# Controller_Sheet.net
KiCad netlist of a schematic drawn in Altium Designer
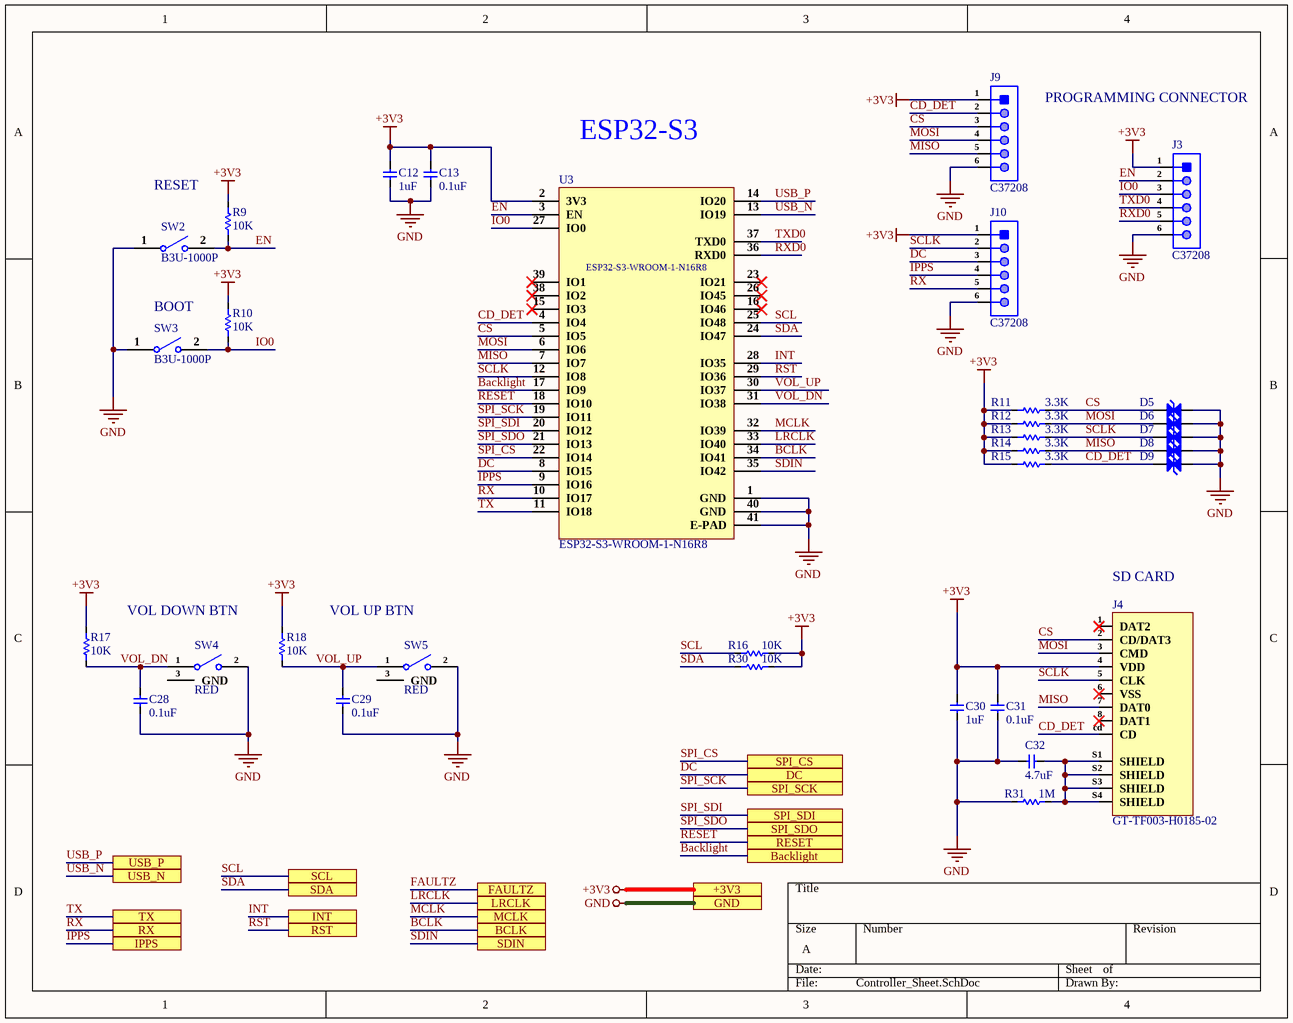
[diagram p0: Controller_Sheet.SchDoc]

(export (version "E")
  (design (tool "Eeschema 10.0.6"))
  (components
    (comp (ref "C12")
      (value "1uF")
      (footprint "Cap-0603")
      (description "CAP CER 1UF 25V X5R 0603")
      (fields
        (field (name "MANUFACTURER") "Yageo")
        (field (name "MANUFACTURER PART NUMBER") "CC0603KRX5R8BB105")
      )
      (libsource (lib "DigitalAzanClock") (part "CC0603KRX5R8BB105"))
    )
    (comp (ref "C13")
      (value "0.1uF")
      (footprint "Cap-0603")
      (description "CAP CER 0.1UF 100V X7R 0603")
      (fields
        (field (name "MANUFACTURER") "Yageo")
        (field (name "MANUFACTURER PART NUMBER") "CC0603KRX7R0BB104")
      )
      (libsource (lib "DigitalAzanClock") (part "CC0603KRX7R0BB104"))
    )
    (comp (ref "C28")
      (value "0.1uF")
      (footprint "Cap-0603")
      (description "CAP CER 0.1UF 100V X7R 0603")
      (fields
        (field (name "MANUFACTURER") "Yageo")
        (field (name "MANUFACTURER PART NUMBER") "CC0603KRX7R0BB104")
      )
      (libsource (lib "DigitalAzanClock") (part "CC0603KRX7R0BB104"))
    )
    (comp (ref "C29")
      (value "0.1uF")
      (footprint "Cap-0603")
      (description "CAP CER 0.1UF 100V X7R 0603")
      (fields
        (field (name "MANUFACTURER") "Yageo")
        (field (name "MANUFACTURER PART NUMBER") "CC0603KRX7R0BB104")
      )
      (libsource (lib "DigitalAzanClock") (part "CC0603KRX7R0BB104"))
    )
    (comp (ref "C30")
      (value "1uF")
      (footprint "Cap-0603")
      (description "CAP CER 1UF 25V X5R 0603")
      (fields
        (field (name "MANUFACTURER") "Yageo")
        (field (name "MANUFACTURER PART NUMBER") "CC0603KRX5R8BB105")
      )
      (libsource (lib "DigitalAzanClock") (part "CC0603KRX5R8BB105"))
    )
    (comp (ref "C31")
      (value "0.1uF")
      (footprint "Cap-0603")
      (description "CAP CER 0.1UF 100V X7R 0603")
      (fields
        (field (name "MANUFACTURER") "Yageo")
        (field (name "MANUFACTURER PART NUMBER") "CC0603KRX7R0BB104")
      )
      (libsource (lib "DigitalAzanClock") (part "CC0603KRX7R0BB104"))
    )
    (comp (ref "C32")
      (value "4.7uF")
      (footprint "Cap-0603")
      (description "50V 4.7nF X7R ±10% 0603 Multilayer Ceramic Capacitors MLCC - SMD/SMT ROHS")
      (fields
        (field (name "MANUFACTURER") "YAGEO")
        (field (name "MANUFACTURER PART NUMBER") "CC0603KRX7R9BB472")
      )
      (libsource (lib "DigitalAzanClock") (part "CC0603KRX7R9BB472"))
    )
    (comp (ref "D5")
      (value "ESD9X5VU")
      (footprint "DFN1006-2L_")
      (description "DFN1006-2 ESD Protection Devices ROHS")
      (fields (field (name "MANUFACTURER") "TECH PUBLIC") (field (name "LCSC PART NUMBER") "C2875160"))
      (libsource (lib "DigitalAzanClock") (part "ESD9X5VU"))
    )
    (comp (ref "D6")
      (value "ESD9X5VU")
      (footprint "DFN1006-2L_")
      (description "DFN1006-2 ESD Protection Devices ROHS")
      (fields (field (name "MANUFACTURER") "TECH PUBLIC") (field (name "LCSC PART NUMBER") "C2875160"))
      (libsource (lib "DigitalAzanClock") (part "ESD9X5VU"))
    )
    (comp (ref "D7")
      (value "ESD9X5VU")
      (footprint "DFN1006-2L_")
      (description "DFN1006-2 ESD Protection Devices ROHS")
      (fields (field (name "MANUFACTURER") "TECH PUBLIC") (field (name "LCSC PART NUMBER") "C2875160"))
      (libsource (lib "DigitalAzanClock") (part "ESD9X5VU"))
    )
    (comp (ref "D8")
      (value "ESD9X5VU")
      (footprint "DFN1006-2L_")
      (description "DFN1006-2 ESD Protection Devices ROHS")
      (fields (field (name "MANUFACTURER") "TECH PUBLIC") (field (name "LCSC PART NUMBER") "C2875160"))
      (libsource (lib "DigitalAzanClock") (part "ESD9X5VU"))
    )
    (comp (ref "D9")
      (value "ESD9X5VU")
      (footprint "DFN1006-2L_")
      (description "DFN1006-2 ESD Protection Devices ROHS")
      (fields (field (name "MANUFACTURER") "TECH PUBLIC") (field (name "LCSC PART NUMBER") "C2875160"))
      (libsource (lib "DigitalAzanClock") (part "ESD9X5VU"))
    )
    (comp (ref "J3")
      (value "C37208")
      (footprint "HDR1X6_")
      (description "Straight 1 6 2.54mm Black Brass Plugin,P=2.54mm Pin Headers ROHS")
      (fields (field (name "MANUFACTURER") "BOOMELEC"))
      (libsource (lib "DigitalAzanClock") (part "C37208"))
    )
    (comp (ref "J4")
      (value "GT-TF003-H0185-02")
      (footprint "GT-TF003-H0185-02")
      (fields (field (name "MANUFACTURER") "G-Switch") (field (name "LCSC PART NUMBER") "C5155564"))
      (libsource (lib "DigitalAzanClock") (part "GT-TF003-H0185-02"))
    )
    (comp (ref "J9")
      (value "C37208")
      (footprint "HDR1X6_")
      (description "Straight 1 6 2.54mm Black Brass Plugin,P=2.54mm Pin Headers ROHS")
      (fields (field (name "MANUFACTURER") "BOOMELEC"))
      (libsource (lib "eSpark Libraries") (part "C37208"))
    )
    (comp (ref "J10")
      (value "C37208")
      (footprint "HDR1X6_")
      (description "Straight 1 6 2.54mm Black Brass Plugin,P=2.54mm Pin Headers ROHS")
      (fields (field (name "MANUFACTURER") "BOOMELEC"))
      (libsource (lib "eSpark Libraries") (part "C37208"))
    )
    (comp (ref "R9")
      (value "10K")
      (footprint "Res-0603")
      (description "RES SMD 10K OHM 0.1% 1/10W 0603")
      (fields
        (field (name "MANUFACTURER") "Yageo")
        (field (name "MANUFACTURER PART NUMBER") "RT0603BRD0710KL")
      )
      (libsource (lib "DigitalAzanClock") (part "RT0603BRD0710KL"))
    )
    (comp (ref "R10")
      (value "10K")
      (footprint "Res-0603")
      (description "RES SMD 10K OHM 0.1% 1/10W 0603")
      (fields
        (field (name "MANUFACTURER") "Yageo")
        (field (name "MANUFACTURER PART NUMBER") "RT0603BRD0710KL")
      )
      (libsource (lib "DigitalAzanClock") (part "RT0603BRD0710KL"))
    )
    (comp (ref "R11")
      (value "3.3K")
      (footprint "Res-0603")
      (description "100mW Thick Film Resistors 75V ±100ppm/℃ ±1% 3.3kΩ 0603 Chip Resistor - Surface Mount ROHS")
      (fields
        (field (name "MANUFACTURER") "UNI-ROYAL(Uniroyal Elec)")
        (field (name "MANUFACTURER PART NUMBER") "0603WAF3301T5E")
      )
      (libsource (lib "DigitalAzanClock") (part "0603WAF3301T5E"))
    )
    (comp (ref "R12")
      (value "3.3K")
      (footprint "Res-0603")
      (description "100mW Thick Film Resistors 75V ±100ppm/℃ ±1% 3.3kΩ 0603 Chip Resistor - Surface Mount ROHS")
      (fields
        (field (name "MANUFACTURER") "UNI-ROYAL(Uniroyal Elec)")
        (field (name "MANUFACTURER PART NUMBER") "0603WAF3301T5E")
      )
      (libsource (lib "DigitalAzanClock") (part "0603WAF3301T5E"))
    )
    (comp (ref "R13")
      (value "3.3K")
      (footprint "Res-0603")
      (description "100mW Thick Film Resistors 75V ±100ppm/℃ ±1% 3.3kΩ 0603 Chip Resistor - Surface Mount ROHS")
      (fields
        (field (name "MANUFACTURER") "UNI-ROYAL(Uniroyal Elec)")
        (field (name "MANUFACTURER PART NUMBER") "0603WAF3301T5E")
      )
      (libsource (lib "DigitalAzanClock") (part "0603WAF3301T5E"))
    )
    (comp (ref "R14")
      (value "3.3K")
      (footprint "Res-0603")
      (description "100mW Thick Film Resistors 75V ±100ppm/℃ ±1% 3.3kΩ 0603 Chip Resistor - Surface Mount ROHS")
      (fields
        (field (name "MANUFACTURER") "UNI-ROYAL(Uniroyal Elec)")
        (field (name "MANUFACTURER PART NUMBER") "0603WAF3301T5E")
      )
      (libsource (lib "DigitalAzanClock") (part "0603WAF3301T5E"))
    )
    (comp (ref "R15")
      (value "3.3K")
      (footprint "Res-0603")
      (description "100mW Thick Film Resistors 75V ±100ppm/℃ ±1% 3.3kΩ 0603 Chip Resistor - Surface Mount ROHS")
      (fields
        (field (name "MANUFACTURER") "UNI-ROYAL(Uniroyal Elec)")
        (field (name "MANUFACTURER PART NUMBER") "0603WAF3301T5E")
      )
      (libsource (lib "DigitalAzanClock") (part "0603WAF3301T5E"))
    )
    (comp (ref "R16")
      (value "10K")
      (footprint "Res-0603")
      (description "RES SMD 10K OHM 0.1% 1/10W 0603")
      (fields
        (field (name "MANUFACTURER") "Yageo")
        (field (name "MANUFACTURER PART NUMBER") "RT0603BRD0710KL")
      )
      (libsource (lib "DigitalAzanClock") (part "RT0603BRD0710KL"))
    )
    (comp (ref "R17")
      (value "10K")
      (footprint "Res-0603")
      (description "RES SMD 10K OHM 0.1% 1/10W 0603")
      (fields
        (field (name "MANUFACTURER") "Yageo")
        (field (name "MANUFACTURER PART NUMBER") "RT0603BRD0710KL")
      )
      (libsource (lib "DigitalAzanClock") (part "RT0603BRD0710KL"))
    )
    (comp (ref "R18")
      (value "10K")
      (footprint "Res-0603")
      (description "RES SMD 10K OHM 0.1% 1/10W 0603")
      (fields
        (field (name "MANUFACTURER") "Yageo")
        (field (name "MANUFACTURER PART NUMBER") "RT0603BRD0710KL")
      )
      (libsource (lib "DigitalAzanClock") (part "RT0603BRD0710KL"))
    )
    (comp (ref "R30")
      (value "10K")
      (footprint "Res-0603")
      (description "RES SMD 10K OHM 0.1% 1/10W 0603")
      (fields
        (field (name "MANUFACTURER") "Yageo")
        (field (name "MANUFACTURER PART NUMBER") "RT0603BRD0710KL")
      )
      (libsource (lib "DigitalAzanClock") (part "RT0603BRD0710KL"))
    )
    (comp (ref "R31")
      (value "1M")
      (footprint "Res-0402")
      (description "RES SMD 1M OHM 5% 1/16W 0402")
      (fields
        (field (name "MANUFACTURER") "Yageo")
        (field (name "MANUFACTURER PART NUMBER") "AF0402JR-071ML")
      )
      (libsource (lib "DigitalAzanClock") (part "AF0402JR-071ML"))
    )
    (comp (ref "SW2")
      (value "B3U-1000P")
      (footprint "B3U-1000P")
      (description "SWITCH TACTILE SPST-NO 0.05A 12V")
      (fields (field (name "MANUFACTURER") "Omron") (field (name "LCSC PART NUMBER") "C231329"))
      (libsource (lib "DigitalAzanClock") (part "B3U-1000P"))
    )
    (comp (ref "SW3")
      (value "B3U-1000P")
      (footprint "B3U-1000P")
      (description "SWITCH TACTILE SPST-NO 0.05A 12V")
      (fields (field (name "MANUFACTURER") "Omron") (field (name "LCSC PART NUMBER") "C231329"))
      (libsource (lib "DigitalAzanClock") (part "B3U-1000P"))
    )
    (comp (ref "SW4")
      (value "RED")
      (footprint "PTS645VK83-2 LFS_")
      (description "SWITCH TACTILE SPST-NO 0.05A 12V")
      (fields
        (field (name "MANUFACTURER") "ITT C&K")
        (field (name "MANUFACTURER PART NUMBER") "PTS645VK83-2LFS")
      )
      (libsource (lib "DigitalAzanClock") (part "PTS645VK83-2 LFS"))
    )
    (comp (ref "SW5")
      (value "RED")
      (footprint "PTS645VK83-2 LFS_")
      (description "SWITCH TACTILE SPST-NO 0.05A 12V")
      (fields
        (field (name "MANUFACTURER") "ITT C&K")
        (field (name "MANUFACTURER PART NUMBER") "PTS645VK83-2LFS")
      )
      (libsource (lib "DigitalAzanClock") (part "PTS645VK83-2 LFS"))
    )
    (comp (ref "U3")
      (value "ESP32-S3-WROOM-1-N16R8")
      (footprint "41-SMD Module")
      (description "ESP32-S3 chip 2.4GHz SMD,18x25.5mm WiFi Modules ROHS")
      (fields
        (field (name "MANUFACTURER") "Expressif System")
        (field (name "MANUFACTURER PART NUMBER") "ESP32-S3-WROOM-1-N8")
      )
      (libsource (lib "DigitalAzanClock") (part "ESP32-S3-WROOM-1-N16R8"))
    )
  )
  (nets
    (net (code "1") (name "+3V3") (class "Default")
      (node (ref "C12") (pin "2") (pinfunction "2_2") (pintype "passive"))
      (node (ref "C13") (pin "2") (pinfunction "2_2") (pintype "passive"))
      (node (ref "C30") (pin "2") (pinfunction "2_2") (pintype "passive"))
      (node (ref "C31") (pin "2") (pinfunction "2_2") (pintype "passive"))
      (node (ref "J10") (pin "1") (pinfunction "1_1") (pintype "passive"))
      (node (ref "J3") (pin "1") (pinfunction "1_1") (pintype "passive"))
      (node (ref "J4") (pin "4") (pinfunction "VDD_4") (pintype "passive"))
      (node (ref "J9") (pin "1") (pinfunction "1_1") (pintype "passive"))
      (node (ref "R10") (pin "2") (pinfunction "2_2") (pintype "passive"))
      (node (ref "R11") (pin "1") (pinfunction "1_1") (pintype "passive"))
      (node (ref "R12") (pin "1") (pinfunction "1_1") (pintype "passive"))
      (node (ref "R13") (pin "1") (pinfunction "1_1") (pintype "passive"))
      (node (ref "R14") (pin "1") (pinfunction "1_1") (pintype "passive"))
      (node (ref "R15") (pin "1") (pinfunction "1_1") (pintype "passive"))
      (node (ref "R16") (pin "1") (pinfunction "1_1") (pintype "passive"))
      (node (ref "R17") (pin "2") (pinfunction "2_2") (pintype "passive"))
      (node (ref "R18") (pin "2") (pinfunction "2_2") (pintype "passive"))
      (node (ref "R30") (pin "1") (pinfunction "1_1") (pintype "passive"))
      (node (ref "R9") (pin "2") (pinfunction "2_2") (pintype "passive"))
      (node (ref "U3") (pin "2") (pinfunction "3V3_2") (pintype "passive"))
    )
    (net (code "2") (name "/BCLK") (class "Default")
      (node (ref "U3") (pin "34") (pinfunction "IO41_34") (pintype "passive"))
    )
    (net (code "3") (name "/Backlight") (class "Default")
      (node (ref "U3") (pin "17") (pinfunction "IO9_17") (pintype "passive"))
    )
    (net (code "4") (name "/CD_DET") (class "Default")
      (node (ref "D9") (pin "1") (pinfunction "A_1") (pintype "passive"))
      (node (ref "J4") (pin "cd") (pinfunction "CD_cd") (pintype "passive"))
      (node (ref "J9") (pin "2") (pinfunction "2_2") (pintype "passive"))
      (node (ref "R15") (pin "2") (pinfunction "2_2") (pintype "passive"))
      (node (ref "U3") (pin "4") (pinfunction "IO4_4") (pintype "passive"))
    )
    (net (code "5") (name "/CS") (class "Default")
      (node (ref "D5") (pin "1") (pinfunction "A_1") (pintype "passive"))
      (node (ref "J4") (pin "2") (pinfunction "CD/DAT3_2") (pintype "passive"))
      (node (ref "J9") (pin "3") (pinfunction "3_3") (pintype "passive"))
      (node (ref "R11") (pin "2") (pinfunction "2_2") (pintype "passive"))
      (node (ref "U3") (pin "5") (pinfunction "IO5_5") (pintype "passive"))
    )
    (net (code "6") (name "/DC") (class "Default")
      (node (ref "J10") (pin "3") (pinfunction "3_3") (pintype "passive"))
      (node (ref "U3") (pin "8") (pinfunction "IO15_8") (pintype "passive"))
    )
    (net (code "7") (name "/EN") (class "Default")
      (node (ref "J3") (pin "2") (pinfunction "2_2") (pintype "passive"))
      (node (ref "R9") (pin "1") (pinfunction "1_1") (pintype "passive"))
      (node (ref "SW2") (pin "2") (pinfunction "2_2") (pintype "passive"))
      (node (ref "U3") (pin "3") (pinfunction "EN_3") (pintype "passive"))
    )
    (net (code "9") (name "/INT") (class "Default")
      (node (ref "U3") (pin "28") (pinfunction "IO35_28") (pintype "passive"))
    )
    (net (code "10") (name "/IO0") (class "Default")
      (node (ref "J3") (pin "3") (pinfunction "3_3") (pintype "passive"))
      (node (ref "R10") (pin "1") (pinfunction "1_1") (pintype "passive"))
      (node (ref "SW3") (pin "2") (pinfunction "2_2") (pintype "passive"))
      (node (ref "U3") (pin "27") (pinfunction "IO0_27") (pintype "passive"))
    )
    (net (code "11") (name "/IPPS") (class "Default")
      (node (ref "J10") (pin "4") (pinfunction "4_4") (pintype "passive"))
      (node (ref "U3") (pin "9") (pinfunction "IO16_9") (pintype "passive"))
    )
    (net (code "12") (name "/LRCLK") (class "Default")
      (node (ref "U3") (pin "33") (pinfunction "IO40_33") (pintype "passive"))
    )
    (net (code "13") (name "/MCLK") (class "Default")
      (node (ref "U3") (pin "32") (pinfunction "IO39_32") (pintype "passive"))
    )
    (net (code "14") (name "/MISO") (class "Default")
      (node (ref "D8") (pin "1") (pinfunction "A_1") (pintype "passive"))
      (node (ref "J4") (pin "7") (pinfunction "DAT0_7") (pintype "passive"))
      (node (ref "J9") (pin "5") (pinfunction "5_5") (pintype "passive"))
      (node (ref "R14") (pin "2") (pinfunction "2_2") (pintype "passive"))
      (node (ref "U3") (pin "7") (pinfunction "IO7_7") (pintype "passive"))
    )
    (net (code "15") (name "/MOSI") (class "Default")
      (node (ref "D6") (pin "1") (pinfunction "A_1") (pintype "passive"))
      (node (ref "J4") (pin "3") (pinfunction "CMD_3") (pintype "passive"))
      (node (ref "J9") (pin "4") (pinfunction "4_4") (pintype "passive"))
      (node (ref "R12") (pin "2") (pinfunction "2_2") (pintype "passive"))
      (node (ref "U3") (pin "6") (pinfunction "IO6_6") (pintype "passive"))
    )
    (net (code "16") (name "/RESET") (class "Default")
      (node (ref "U3") (pin "18") (pinfunction "IO10_18") (pintype "passive"))
    )
    (net (code "17") (name "/RST") (class "Default")
      (node (ref "U3") (pin "29") (pinfunction "IO36_29") (pintype "passive"))
    )
    (net (code "18") (name "/RX") (class "Default")
      (node (ref "J10") (pin "5") (pinfunction "5_5") (pintype "passive"))
      (node (ref "U3") (pin "10") (pinfunction "IO17_10") (pintype "passive"))
    )
    (net (code "19") (name "/RXD0") (class "Default")
      (node (ref "J3") (pin "5") (pinfunction "5_5") (pintype "passive"))
      (node (ref "U3") (pin "36") (pinfunction "RXD0_36") (pintype "passive"))
    )
    (net (code "20") (name "/SCL") (class "Default")
      (node (ref "R16") (pin "2") (pinfunction "2_2") (pintype "passive"))
      (node (ref "U3") (pin "25") (pinfunction "IO48_25") (pintype "passive"))
    )
    (net (code "21") (name "/SCLK") (class "Default")
      (node (ref "D7") (pin "1") (pinfunction "A_1") (pintype "passive"))
      (node (ref "J10") (pin "2") (pinfunction "2_2") (pintype "passive"))
      (node (ref "J4") (pin "5") (pinfunction "CLK_5") (pintype "passive"))
      (node (ref "R13") (pin "2") (pinfunction "2_2") (pintype "passive"))
      (node (ref "U3") (pin "12") (pinfunction "IO8_12") (pintype "passive"))
    )
    (net (code "22") (name "/SDA") (class "Default")
      (node (ref "R30") (pin "2") (pinfunction "2_2") (pintype "passive"))
      (node (ref "U3") (pin "24") (pinfunction "IO47_24") (pintype "passive"))
    )
    (net (code "23") (name "/SDIN") (class "Default")
      (node (ref "U3") (pin "35") (pinfunction "IO42_35") (pintype "passive"))
    )
    (net (code "24") (name "/SPI_CS") (class "Default")
      (node (ref "U3") (pin "22") (pinfunction "IO14_22") (pintype "passive"))
    )
    (net (code "25") (name "/SPI_SCK") (class "Default")
      (node (ref "U3") (pin "19") (pinfunction "IO11_19") (pintype "passive"))
    )
    (net (code "26") (name "/SPI_SDI") (class "Default")
      (node (ref "U3") (pin "20") (pinfunction "IO12_20") (pintype "passive"))
    )
    (net (code "27") (name "/SPI_SDO") (class "Default")
      (node (ref "U3") (pin "21") (pinfunction "IO13_21") (pintype "passive"))
    )
    (net (code "28") (name "/TX") (class "Default")
      (node (ref "U3") (pin "11") (pinfunction "IO18_11") (pintype "passive"))
    )
    (net (code "29") (name "/TXD0") (class "Default")
      (node (ref "J3") (pin "4") (pinfunction "4_4") (pintype "passive"))
      (node (ref "U3") (pin "37") (pinfunction "TXD0_37") (pintype "passive"))
    )
    (net (code "30") (name "/USB_N") (class "Default")
      (node (ref "U3") (pin "13") (pinfunction "IO19_13") (pintype "passive"))
    )
    (net (code "31") (name "/USB_P") (class "Default")
      (node (ref "U3") (pin "14") (pinfunction "IO20_14") (pintype "passive"))
    )
    (net (code "32") (name "/VOL_DN") (class "Default")
      (node (ref "C28") (pin "2") (pinfunction "2_2") (pintype "passive"))
      (node (ref "R17") (pin "1") (pinfunction "1_1") (pintype "passive"))
      (node (ref "SW4") (pin "1") (pinfunction "1_1") (pintype "passive"))
      (node (ref "U3") (pin "31") (pinfunction "IO38_31") (pintype "passive"))
    )
    (net (code "33") (name "/VOL_UP") (class "Default")
      (node (ref "C29") (pin "2") (pinfunction "2_2") (pintype "passive"))
      (node (ref "R18") (pin "1") (pinfunction "1_1") (pintype "passive"))
      (node (ref "SW5") (pin "1") (pinfunction "1_1") (pintype "passive"))
      (node (ref "U3") (pin "30") (pinfunction "IO37_30") (pintype "passive"))
    )
    (net (code "34") (name "GND") (class "Default")
      (node (ref "C12") (pin "1") (pinfunction "1_1") (pintype "passive"))
      (node (ref "C13") (pin "1") (pinfunction "1_1") (pintype "passive"))
      (node (ref "C28") (pin "1") (pinfunction "1_1") (pintype "passive"))
      (node (ref "C29") (pin "1") (pinfunction "1_1") (pintype "passive"))
      (node (ref "C30") (pin "1") (pinfunction "1_1") (pintype "passive"))
      (node (ref "C31") (pin "1") (pinfunction "1_1") (pintype "passive"))
      (node (ref "C32") (pin "2") (pinfunction "2_2") (pintype "passive"))
      (node (ref "D5") (pin "2") (pinfunction "A_2") (pintype "passive"))
      (node (ref "D6") (pin "2") (pinfunction "A_2") (pintype "passive"))
      (node (ref "D7") (pin "2") (pinfunction "A_2") (pintype "passive"))
      (node (ref "D8") (pin "2") (pinfunction "A_2") (pintype "passive"))
      (node (ref "D9") (pin "2") (pinfunction "A_2") (pintype "passive"))
      (node (ref "J10") (pin "6") (pinfunction "6_6") (pintype "passive"))
      (node (ref "J3") (pin "6") (pinfunction "6_6") (pintype "passive"))
      (node (ref "J9") (pin "6") (pinfunction "6_6") (pintype "passive"))
      (node (ref "R31") (pin "2") (pinfunction "2_2") (pintype "passive"))
      (node (ref "SW2") (pin "1") (pinfunction "1_1") (pintype "passive"))
      (node (ref "SW3") (pin "1") (pinfunction "1_1") (pintype "passive"))
      (node (ref "SW4") (pin "2") (pinfunction "2_2") (pintype "passive"))
      (node (ref "SW5") (pin "2") (pinfunction "2_2") (pintype "passive"))
      (node (ref "U3") (pin "1") (pinfunction "GND_1") (pintype "passive"))
      (node (ref "U3") (pin "40") (pinfunction "GND_40") (pintype "passive"))
      (node (ref "U3") (pin "41") (pinfunction "E-PAD_41") (pintype "passive"))
    )
    (net (code "35") (name "Net-(C32-Pad1)") (class "Default")
      (node (ref "C32") (pin "1") (pinfunction "1_1") (pintype "passive"))
      (node (ref "J4") (pin "S1") (pinfunction "SHIELD_S1") (pintype "passive"))
      (node (ref "J4") (pin "S2") (pinfunction "SHIELD_S2") (pintype "passive"))
      (node (ref "J4") (pin "S3") (pinfunction "SHIELD_S3") (pintype "passive"))
      (node (ref "J4") (pin "S4") (pinfunction "SHIELD_S4") (pintype "passive"))
      (node (ref "R31") (pin "1") (pinfunction "1_1") (pintype "passive"))
    )
    (net (code "36") (name "unconnected-(J4-DAT1-Pad8)") (class "Default")
      (node (ref "J4") (pin "8") (pinfunction "DAT1_8") (pintype "passive+no_connect"))
    )
    (net (code "37") (name "unconnected-(J4-DAT2-Pad1)") (class "Default")
      (node (ref "J4") (pin "1") (pinfunction "DAT2_1") (pintype "passive+no_connect"))
    )
    (net (code "38") (name "unconnected-(J4-VSS-Pad6)") (class "Default")
      (node (ref "J4") (pin "6") (pinfunction "VSS_6") (pintype "passive+no_connect"))
    )
    (net (code "39") (name "unconnected-(SW4-GND-Pad3)") (class "Default")
      (node (ref "SW4") (pin "3") (pinfunction "GND_3") (pintype "passive"))
    )
    (net (code "40") (name "unconnected-(SW5-GND-Pad3)") (class "Default")
      (node (ref "SW5") (pin "3") (pinfunction "GND_3") (pintype "passive"))
    )
    (net (code "41") (name "unconnected-(U3-IO1-Pad39)") (class "Default")
      (node (ref "U3") (pin "39") (pinfunction "IO1_39") (pintype "passive+no_connect"))
    )
    (net (code "42") (name "unconnected-(U3-IO2-Pad38)") (class "Default")
      (node (ref "U3") (pin "38") (pinfunction "IO2_38") (pintype "passive+no_connect"))
    )
    (net (code "43") (name "unconnected-(U3-IO3-Pad15)") (class "Default")
      (node (ref "U3") (pin "15") (pinfunction "IO3_15") (pintype "passive+no_connect"))
    )
    (net (code "44") (name "unconnected-(U3-IO21-Pad23)") (class "Default")
      (node (ref "U3") (pin "23") (pinfunction "IO21_23") (pintype "passive+no_connect"))
    )
    (net (code "45") (name "unconnected-(U3-IO45-Pad26)") (class "Default")
      (node (ref "U3") (pin "26") (pinfunction "IO45_26") (pintype "passive+no_connect"))
    )
    (net (code "46") (name "unconnected-(U3-IO46-Pad16)") (class "Default")
      (node (ref "U3") (pin "16") (pinfunction "IO46_16") (pintype "passive+no_connect"))
    )
  )
)
